# Alternative1.net
KiCad netlist of a schematic drawn in EAGLE
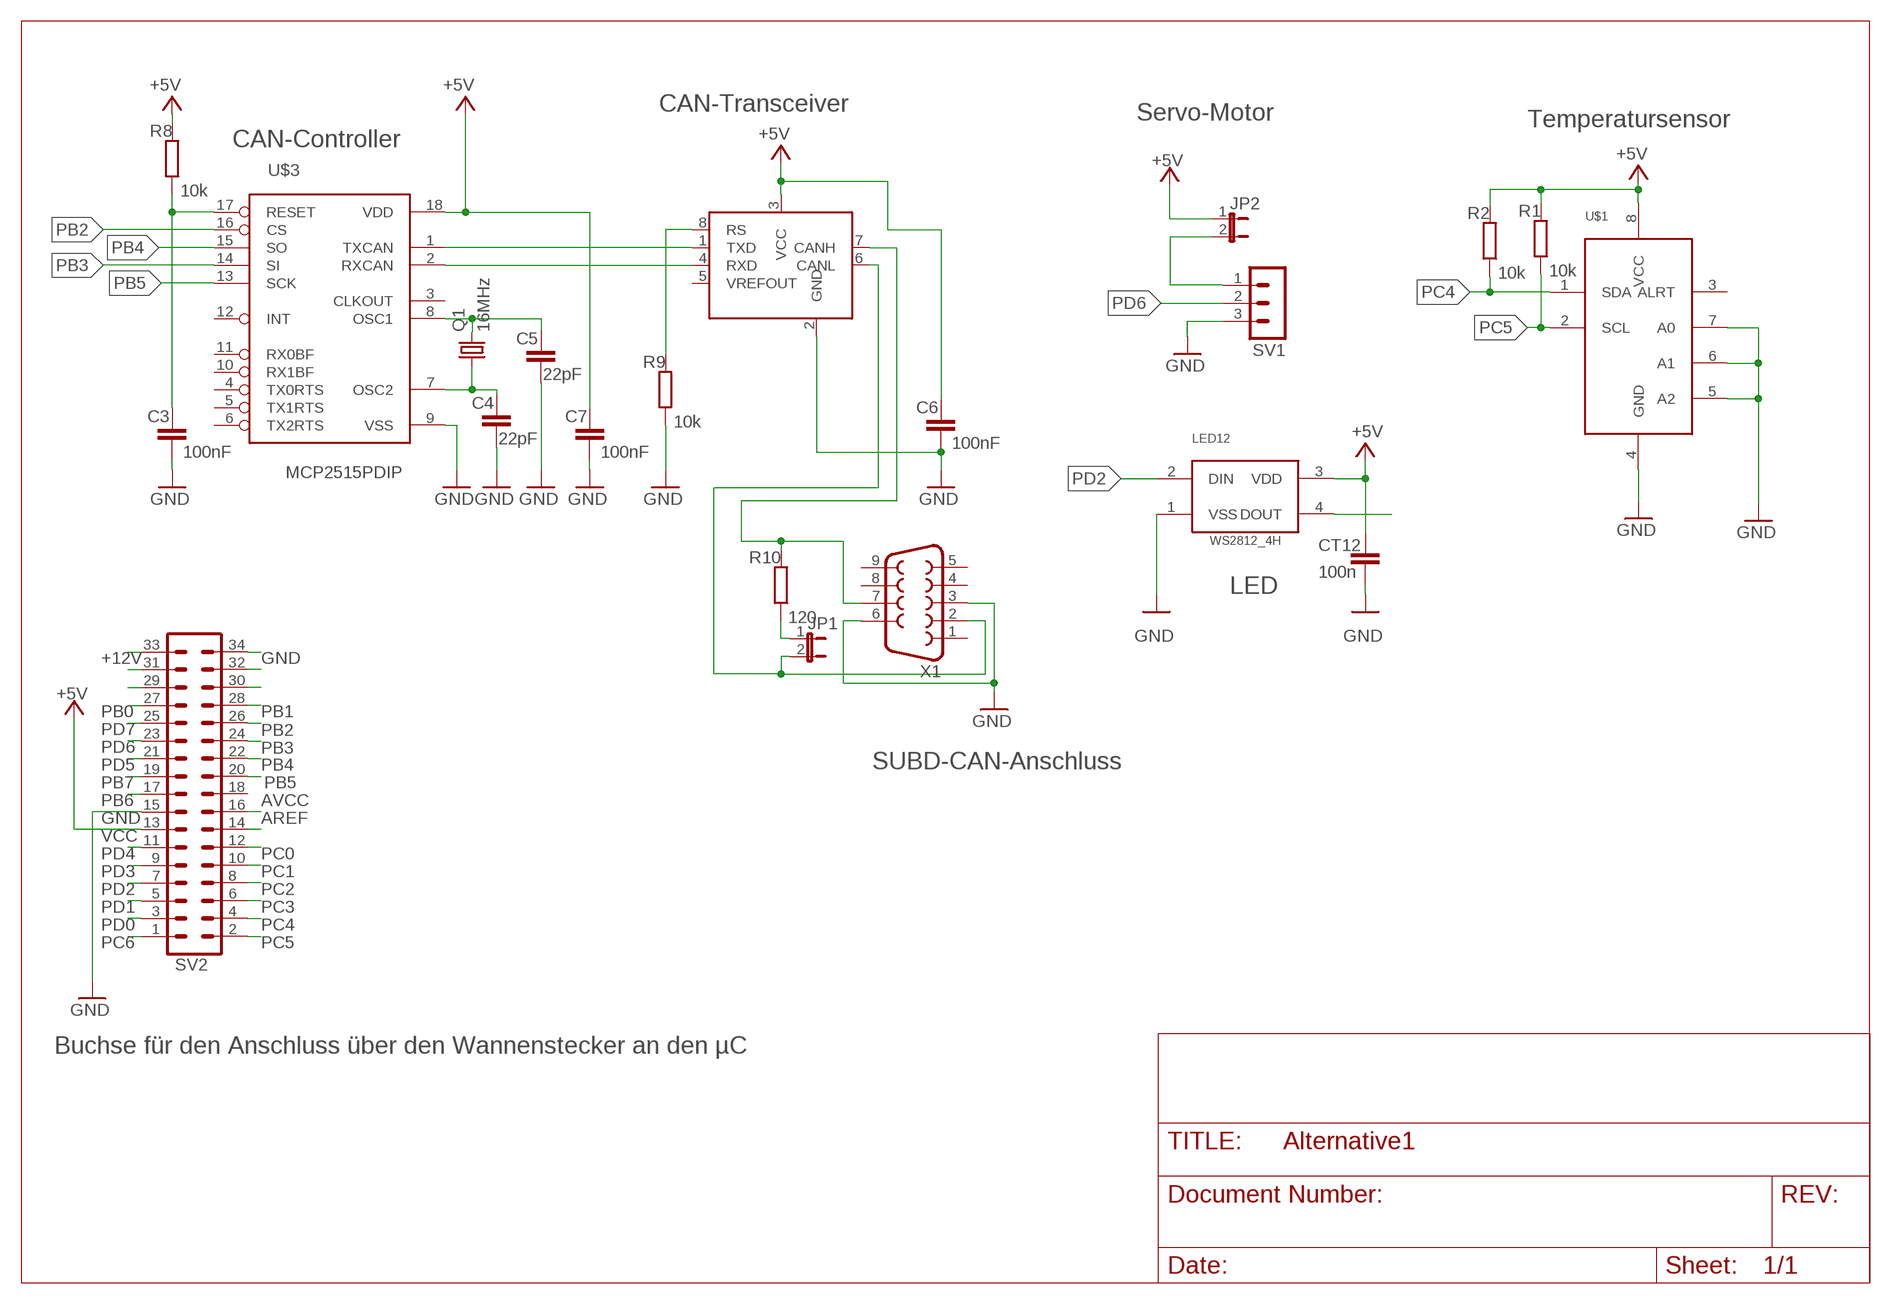
[diagram p0: schematic, sheet 1]

(export (version "E")
  (design (tool "Eeschema 10.0.6"))
  (components
    (comp (ref "C3")
      (value "100nF")
      (footprint "eagle-import:C0805K")
      (libsource (lib "eagle-import") (part "C-EUC0805K"))
    )
    (comp (ref "C4")
      (value "22pF")
      (footprint "eagle-import:C0805K")
      (libsource (lib "eagle-import") (part "C-EUC0805K"))
    )
    (comp (ref "C5")
      (value "22pF")
      (footprint "eagle-import:C0805K")
      (libsource (lib "eagle-import") (part "C-EUC0805K"))
    )
    (comp (ref "C6")
      (value "100nF")
      (footprint "eagle-import:C0805K")
      (libsource (lib "eagle-import") (part "C-EUC0805K"))
    )
    (comp (ref "C7")
      (value "100nF")
      (footprint "eagle-import:C0805K")
      (libsource (lib "eagle-import") (part "C-EUC0805K"))
    )
    (comp (ref "CT12")
      (value "100n")
      (footprint "eagle-import:C0805")
      (libsource (lib "eagle-import") (part "C-EUC0805"))
    )
    (comp (ref "IC2")
      (value "PCA82C251")
      (footprint "eagle-import:SO8")
      (libsource (lib "eagle-import") (part "82C250SMDSMD"))
    )
    (comp (ref "JP1")
      (value "JP1E")
      (footprint "eagle-import:JP1")
      (libsource (lib "eagle-import") (part "JP1E"))
    )
    (comp (ref "JP2")
      (value "JP1E")
      (footprint "eagle-import:JP1")
      (libsource (lib "eagle-import") (part "JP1E"))
    )
    (comp (ref "LED12")
      (value "WS2812_4H")
      (footprint "eagle-import:WS2812_4")
      (libsource (lib "eagle-import") (part "WS2812_4H"))
    )
    (comp (ref "Q1")
      (value "16MHz")
      (footprint "eagle-import:HC49_S")
      (libsource (lib "eagle-import") (part "CRYSTALHC49S"))
    )
    (comp (ref "R1")
      (value "10k")
      (footprint "eagle-import:R0805")
      (libsource (lib "eagle-import") (part "R-EU_R0805"))
    )
    (comp (ref "R2")
      (value "10k")
      (footprint "eagle-import:R0805")
      (libsource (lib "eagle-import") (part "R-EU_R0805"))
    )
    (comp (ref "R8")
      (value "10k")
      (footprint "eagle-import:R0805")
      (libsource (lib "eagle-import") (part "R-EU_R0805"))
    )
    (comp (ref "R9")
      (value "10k")
      (footprint "eagle-import:R0805")
      (libsource (lib "eagle-import") (part "R-EU_R0805"))
    )
    (comp (ref "R10")
      (value "120")
      (footprint "eagle-import:R0805")
      (libsource (lib "eagle-import") (part "R-EU_R0805"))
    )
    (comp (ref "SV1")
      (value "MA03-1")
      (footprint "eagle-import:MA03-1")
      (libsource (lib "eagle-import") (part "MA03-1"))
    )
    (comp (ref "SV2")
      (value "ML34")
      (footprint "eagle-import:ML34")
      (libsource (lib "eagle-import") (part "ML34"))
    )
    (comp (ref "U$1")
      (value "TMP75-SO8")
      (footprint "eagle-import:SO08")
      (libsource (lib "eagle-import") (part "TMP75-SO8"))
    )
    (comp (ref "U$3")
      (value "MCP2515PDIP")
      (footprint "eagle-import:DIL18")
      (libsource (lib "eagle-import") (part "MCP2515PDIP"))
    )
    (comp (ref "X1")
      (value "F09HP")
      (footprint "eagle-import:F09HP")
      (libsource (lib "eagle-import") (part "F09HP"))
    )
  )
  (nets
    (net (code "1") (name "+5V") (class "Default")
      (node (ref "C6") (pin "1") (pinfunction "1_1") (pintype "passive"))
      (node (ref "C7") (pin "1") (pinfunction "1_1") (pintype "passive"))
      (node (ref "CT12") (pin "1") (pinfunction "1_1") (pintype "passive"))
      (node (ref "IC2") (pin "3") (pinfunction "VCC_3") (pintype "power_in"))
      (node (ref "JP2") (pin "1") (pinfunction "1_1") (pintype "passive"))
      (node (ref "LED12") (pin "3") (pinfunction "VDD_3") (pintype "power_in"))
      (node (ref "R1") (pin "2") (pinfunction "2_2") (pintype "passive"))
      (node (ref "R2") (pin "2") (pinfunction "2_2") (pintype "passive"))
      (node (ref "R8") (pin "2") (pinfunction "2_2") (pintype "passive"))
      (node (ref "SV2") (pin "13") (pinfunction "13_13") (pintype "passive"))
      (node (ref "U$1") (pin "8") (pinfunction "VCC_8") (pintype "power_in"))
      (node (ref "U$3") (pin "18") (pinfunction "VDD_18") (pintype "power_in"))
    )
    (net (code "2") (name "/+12V") (class "Default")
      (node (ref "SV2") (pin "33") (pinfunction "33_33") (pintype "passive"))
    )
    (net (code "3") (name "/AREF") (class "Default")
      (node (ref "SV2") (pin "16") (pinfunction "16_16") (pintype "passive"))
    )
    (net (code "4") (name "/PB0") (class "Default")
      (node (ref "SV2") (pin "27") (pinfunction "27_27") (pintype "passive"))
    )
    (net (code "5") (name "/PB1") (class "Default")
      (node (ref "SV2") (pin "28") (pinfunction "28_28") (pintype "passive"))
    )
    (net (code "6") (name "/PB6") (class "Default")
      (node (ref "SV2") (pin "17") (pinfunction "17_17") (pintype "passive"))
    )
    (net (code "7") (name "/PB7") (class "Default")
      (node (ref "SV2") (pin "19") (pinfunction "19_19") (pintype "passive"))
    )
    (net (code "8") (name "/PC0") (class "Default")
      (node (ref "SV2") (pin "12") (pinfunction "12_12") (pintype "passive"))
    )
    (net (code "9") (name "/PC1") (class "Default")
      (node (ref "SV2") (pin "10") (pinfunction "10_10") (pintype "passive"))
    )
    (net (code "10") (name "/PC2") (class "Default")
      (node (ref "SV2") (pin "8") (pinfunction "8_8") (pintype "passive"))
    )
    (net (code "11") (name "/PC3") (class "Default")
      (node (ref "SV2") (pin "6") (pinfunction "6_6") (pintype "passive"))
    )
    (net (code "12") (name "/PC6") (class "Default")
      (node (ref "SV2") (pin "1") (pinfunction "1_1") (pintype "passive"))
    )
    (net (code "13") (name "/PD0") (class "Default")
      (node (ref "SV2") (pin "3") (pinfunction "3_3") (pintype "passive"))
    )
    (net (code "14") (name "/PD1") (class "Default")
      (node (ref "SV2") (pin "5") (pinfunction "5_5") (pintype "passive"))
    )
    (net (code "15") (name "/PD3") (class "Default")
      (node (ref "SV2") (pin "9") (pinfunction "9_9") (pintype "passive"))
    )
    (net (code "16") (name "/PD4") (class "Default")
      (node (ref "SV2") (pin "11") (pinfunction "11_11") (pintype "passive"))
    )
    (net (code "17") (name "/PD5") (class "Default")
      (node (ref "SV2") (pin "21") (pinfunction "21_21") (pintype "passive"))
    )
    (net (code "18") (name "/PD7") (class "Default")
      (node (ref "SV2") (pin "25") (pinfunction "25_25") (pintype "passive"))
    )
    (net (code "19") (name "GND") (class "Default")
      (node (ref "C3") (pin "2") (pinfunction "2_2") (pintype "passive"))
      (node (ref "C4") (pin "2") (pinfunction "2_2") (pintype "passive"))
      (node (ref "C5") (pin "2") (pinfunction "2_2") (pintype "passive"))
      (node (ref "C6") (pin "2") (pinfunction "2_2") (pintype "passive"))
      (node (ref "C7") (pin "2") (pinfunction "2_2") (pintype "passive"))
      (node (ref "CT12") (pin "2") (pinfunction "2_2") (pintype "passive"))
      (node (ref "IC2") (pin "2") (pinfunction "GND_2") (pintype "power_in"))
      (node (ref "LED12") (pin "1") (pinfunction "VSS_1") (pintype "power_in"))
      (node (ref "R9") (pin "1") (pinfunction "1_1") (pintype "passive"))
      (node (ref "SV1") (pin "3") (pinfunction "3_3") (pintype "passive"))
      (node (ref "SV2") (pin "15") (pinfunction "15_15") (pintype "passive"))
      (node (ref "SV2") (pin "34") (pinfunction "34_34") (pintype "passive"))
      (node (ref "U$1") (pin "4") (pinfunction "GND_4") (pintype "power_in"))
      (node (ref "U$1") (pin "5") (pinfunction "A2_5") (pintype "input"))
      (node (ref "U$1") (pin "6") (pinfunction "A1_6") (pintype "input"))
      (node (ref "U$1") (pin "7") (pinfunction "A0_7") (pintype "input"))
      (node (ref "U$3") (pin "9") (pinfunction "VSS_9") (pintype "power_in"))
      (node (ref "X1") (pin "3") (pinfunction "3_3") (pintype "passive"))
      (node (ref "X1") (pin "6") (pinfunction "6_6") (pintype "passive"))
    )
    (net (code "20") (name "Net-(IC2-CANH)") (class "Default")
      (node (ref "IC2") (pin "7") (pinfunction "CANH_7") (pintype "bidirectional"))
      (node (ref "R10") (pin "2") (pinfunction "2_2") (pintype "passive"))
      (node (ref "X1") (pin "7") (pinfunction "7_7") (pintype "passive"))
    )
    (net (code "21") (name "Net-(IC2-CANL)") (class "Default")
      (node (ref "IC2") (pin "6") (pinfunction "CANL_6") (pintype "bidirectional"))
      (node (ref "JP1") (pin "2") (pinfunction "2_2") (pintype "passive"))
      (node (ref "X1") (pin "2") (pinfunction "2_2") (pintype "passive"))
    )
    (net (code "22") (name "Net-(IC2-RS)") (class "Default")
      (node (ref "IC2") (pin "8") (pinfunction "RS_8") (pintype "input"))
      (node (ref "R9") (pin "2") (pinfunction "2_2") (pintype "passive"))
    )
    (net (code "23") (name "Net-(IC2-RXD)") (class "Default")
      (node (ref "IC2") (pin "4") (pinfunction "RXD_4") (pintype "output"))
      (node (ref "U$3") (pin "2") (pinfunction "RXCAN_2") (pintype "input"))
    )
    (net (code "24") (name "Net-(IC2-TXD)") (class "Default")
      (node (ref "IC2") (pin "1") (pinfunction "TXD_1") (pintype "input"))
      (node (ref "U$3") (pin "1") (pinfunction "TXCAN_1") (pintype "output"))
    )
    (net (code "25") (name "Net-(JP1-Pad1)") (class "Default")
      (node (ref "JP1") (pin "1") (pinfunction "1_1") (pintype "passive"))
      (node (ref "R10") (pin "1") (pinfunction "1_1") (pintype "passive"))
    )
    (net (code "26") (name "Net-(JP2-Pad2)") (class "Default")
      (node (ref "JP2") (pin "2") (pinfunction "2_2") (pintype "passive"))
      (node (ref "SV1") (pin "1") (pinfunction "1_1") (pintype "passive"))
    )
    (net (code "27") (name "Net-(U$3-OSC1)") (class "Default")
      (node (ref "C5") (pin "1") (pinfunction "1_1") (pintype "passive"))
      (node (ref "Q1") (pin "2") (pinfunction "2_2") (pintype "passive"))
      (node (ref "U$3") (pin "8") (pinfunction "OSC1_8") (pintype "input"))
    )
    (net (code "28") (name "Net-(U$3-OSC2)") (class "Default")
      (node (ref "C4") (pin "1") (pinfunction "1_1") (pintype "passive"))
      (node (ref "Q1") (pin "1") (pinfunction "1_1") (pintype "passive"))
      (node (ref "U$3") (pin "7") (pinfunction "OSC2_7") (pintype "input"))
    )
    (net (code "29") (name "Net-(U$3-RESET)") (class "Default")
      (node (ref "C3") (pin "1") (pinfunction "1_1") (pintype "passive"))
      (node (ref "R8") (pin "1") (pinfunction "1_1") (pintype "passive"))
      (node (ref "U$3") (pin "17") (pinfunction "RESET_17") (pintype "input"))
    )
    (net (code "30") (name "PB2") (class "Default")
      (node (ref "SV2") (pin "26") (pinfunction "26_26") (pintype "passive"))
      (node (ref "U$3") (pin "16") (pinfunction "CS_16") (pintype "input"))
    )
    (net (code "31") (name "PB3") (class "Default")
      (node (ref "SV2") (pin "24") (pinfunction "24_24") (pintype "passive"))
      (node (ref "U$3") (pin "14") (pinfunction "SI_14") (pintype "input"))
    )
    (net (code "32") (name "PB4") (class "Default")
      (node (ref "SV2") (pin "22") (pinfunction "22_22") (pintype "passive"))
      (node (ref "U$3") (pin "15") (pinfunction "SO_15") (pintype "output"))
    )
    (net (code "33") (name "PB5") (class "Default")
      (node (ref "SV2") (pin "20") (pinfunction "20_20") (pintype "passive"))
      (node (ref "U$3") (pin "13") (pinfunction "SCK_13") (pintype "input"))
    )
    (net (code "34") (name "PC4") (class "Default")
      (node (ref "R2") (pin "1") (pinfunction "1_1") (pintype "passive"))
      (node (ref "SV2") (pin "4") (pinfunction "4_4") (pintype "passive"))
      (node (ref "U$1") (pin "1") (pinfunction "SDA_1") (pintype "bidirectional"))
    )
    (net (code "35") (name "PC5") (class "Default")
      (node (ref "R1") (pin "1") (pinfunction "1_1") (pintype "passive"))
      (node (ref "SV2") (pin "2") (pinfunction "2_2") (pintype "passive"))
      (node (ref "U$1") (pin "2") (pinfunction "SCL_2") (pintype "input"))
    )
    (net (code "36") (name "PD2") (class "Default")
      (node (ref "LED12") (pin "2") (pinfunction "DIN_2") (pintype "input"))
      (node (ref "SV2") (pin "7") (pinfunction "7_7") (pintype "passive"))
    )
    (net (code "37") (name "PD6") (class "Default")
      (node (ref "SV1") (pin "2") (pinfunction "2_2") (pintype "passive"))
      (node (ref "SV2") (pin "23") (pinfunction "23_23") (pintype "passive"))
    )
    (net (code "38") (name "unconnected-(IC2-VREFOUT-Pad5)") (class "Default")
      (node (ref "IC2") (pin "5") (pinfunction "VREFOUT_5") (pintype "output"))
    )
    (net (code "39") (name "unconnected-(LED12-DOUT-Pad4)") (class "Default")
      (node (ref "LED12") (pin "4") (pinfunction "DOUT_4") (pintype "output"))
    )
    (net (code "40") (name "unconnected-(SV2-Pad14)") (class "Default")
      (node (ref "SV2") (pin "14") (pinfunction "14_14") (pintype "passive"))
    )
    (net (code "41") (name "unconnected-(SV2-Pad18)") (class "Default")
      (node (ref "SV2") (pin "18") (pinfunction "18_18") (pintype "passive"))
    )
    (net (code "42") (name "unconnected-(SV2-Pad29)") (class "Default")
      (node (ref "SV2") (pin "29") (pinfunction "29_29") (pintype "passive"))
    )
    (net (code "43") (name "unconnected-(SV2-Pad30)") (class "Default")
      (node (ref "SV2") (pin "30") (pinfunction "30_30") (pintype "passive"))
    )
    (net (code "44") (name "unconnected-(SV2-Pad31)") (class "Default")
      (node (ref "SV2") (pin "31") (pinfunction "31_31") (pintype "passive"))
    )
    (net (code "45") (name "unconnected-(SV2-Pad32)") (class "Default")
      (node (ref "SV2") (pin "32") (pinfunction "32_32") (pintype "passive"))
    )
    (net (code "46") (name "unconnected-(U$1-ALRT-Pad3)") (class "Default")
      (node (ref "U$1") (pin "3") (pinfunction "ALRT_3") (pintype "output"))
    )
    (net (code "47") (name "unconnected-(U$3-CLKOUT-Pad3)") (class "Default")
      (node (ref "U$3") (pin "3") (pinfunction "CLKOUT_3") (pintype "output"))
    )
    (net (code "48") (name "unconnected-(U$3-INT-Pad12)") (class "Default")
      (node (ref "U$3") (pin "12") (pinfunction "INT_12") (pintype "input"))
    )
    (net (code "49") (name "unconnected-(U$3-RX0BF-Pad11)") (class "Default")
      (node (ref "U$3") (pin "11") (pinfunction "RX0BF_11") (pintype "input"))
    )
    (net (code "50") (name "unconnected-(U$3-RX1BF-Pad10)") (class "Default")
      (node (ref "U$3") (pin "10") (pinfunction "RX1BF_10") (pintype "input"))
    )
    (net (code "51") (name "unconnected-(U$3-TX0RTS-Pad4)") (class "Default")
      (node (ref "U$3") (pin "4") (pinfunction "TX0RTS_4") (pintype "output"))
    )
    (net (code "52") (name "unconnected-(U$3-TX1RTS-Pad5)") (class "Default")
      (node (ref "U$3") (pin "5") (pinfunction "TX1RTS_5") (pintype "output"))
    )
    (net (code "53") (name "unconnected-(U$3-TX2RTS-Pad6)") (class "Default")
      (node (ref "U$3") (pin "6") (pinfunction "TX2RTS_6") (pintype "output"))
    )
    (net (code "54") (name "unconnected-(X1-Pad1)") (class "Default")
      (node (ref "X1") (pin "1") (pinfunction "1_1") (pintype "passive"))
    )
    (net (code "55") (name "unconnected-(X1-Pad4)") (class "Default")
      (node (ref "X1") (pin "4") (pinfunction "4_4") (pintype "passive"))
    )
    (net (code "56") (name "unconnected-(X1-Pad5)") (class "Default")
      (node (ref "X1") (pin "5") (pinfunction "5_5") (pintype "passive"))
    )
    (net (code "57") (name "unconnected-(X1-Pad8)") (class "Default")
      (node (ref "X1") (pin "8") (pinfunction "8_8") (pintype "passive"))
    )
    (net (code "58") (name "unconnected-(X1-Pad9)") (class "Default")
      (node (ref "X1") (pin "9") (pinfunction "9_9") (pintype "passive"))
    )
  )
)
